# double-tube-iv.net
KiCad netlist of a schematic drawn in EAGLE
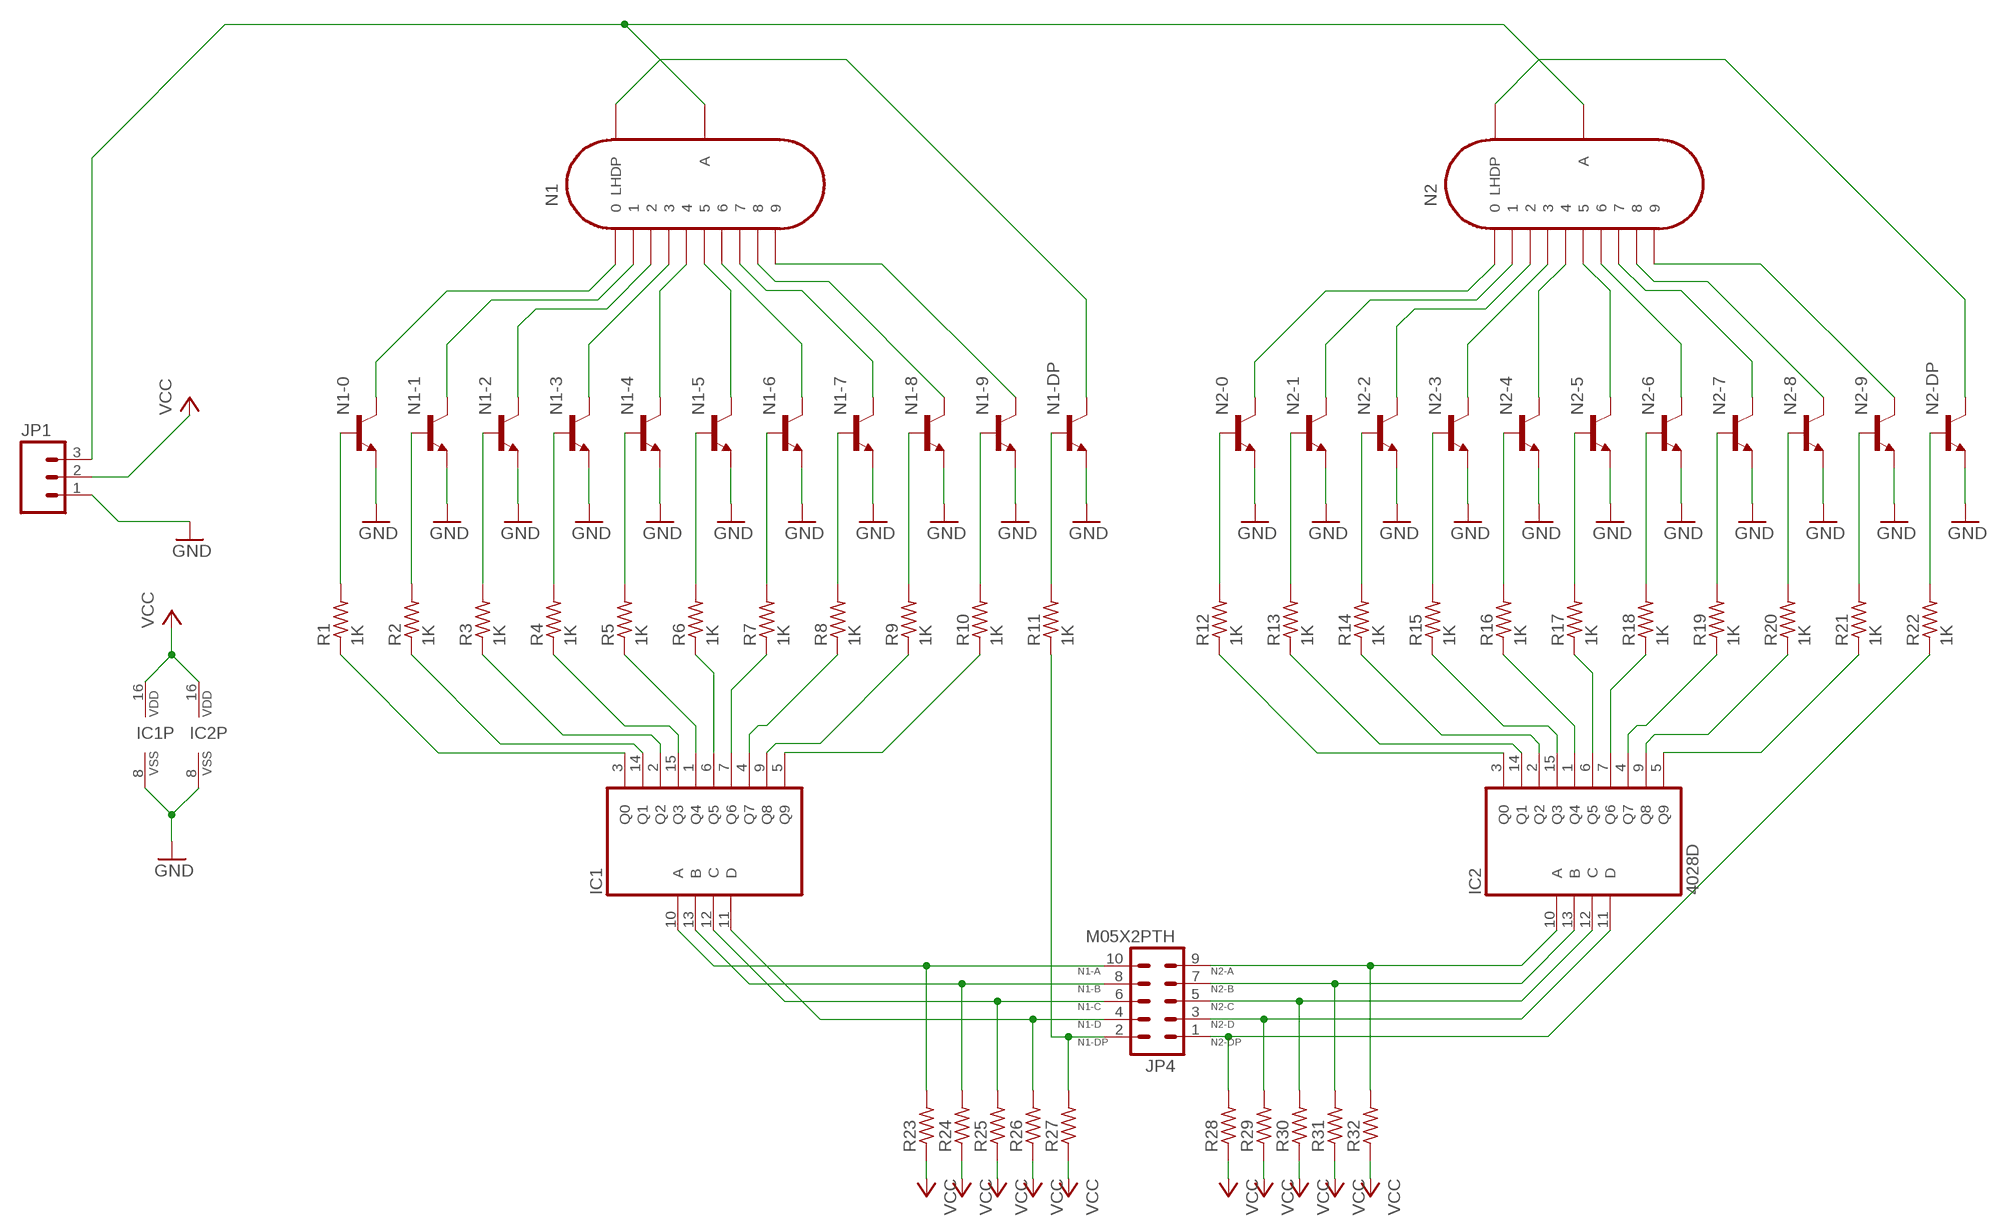
[diagram p0: schematic, sheet 1]

(export (version "E")
  (design (tool "Eeschema 10.0.6"))
  (components
    (comp (ref "IC1")
      (value "4028D")
      (footprint "eagle-import:SO16")
      (libsource (lib "eagle-import") (part "4028D"))
    )
    (comp (ref "IC2")
      (value "4028D")
      (footprint "eagle-import:SO16")
      (libsource (lib "eagle-import") (part "4028D"))
    )
    (comp (ref "JP1")
      (value "M03PTH")
      (footprint "eagle-import:1X03")
      (libsource (lib "eagle-import") (part "M03PTH"))
    )
    (comp (ref "JP4")
      (value "M05X2PTH")
      (footprint "eagle-import:AVR_ICSP")
      (libsource (lib "eagle-import") (part "M05X2PTH"))
    )
    (comp (ref "N1")
      (value "IN-12B")
      (footprint "eagle-import:IN-12")
      (libsource (lib "eagle-import") (part "IN-12B"))
    )
    (comp (ref "N1-0")
      (value "NPN_SMD")
      (footprint "eagle-import:SOT-23")
      (libsource (lib "eagle-import") (part "NPN_SMD"))
    )
    (comp (ref "N1-1")
      (value "NPN_SMD")
      (footprint "eagle-import:SOT-23")
      (libsource (lib "eagle-import") (part "NPN_SMD"))
    )
    (comp (ref "N1-2")
      (value "NPN_SMD")
      (footprint "eagle-import:SOT-23")
      (libsource (lib "eagle-import") (part "NPN_SMD"))
    )
    (comp (ref "N1-3")
      (value "NPN_SMD")
      (footprint "eagle-import:SOT-23")
      (libsource (lib "eagle-import") (part "NPN_SMD"))
    )
    (comp (ref "N1-4")
      (value "NPN_SMD")
      (footprint "eagle-import:SOT-23")
      (libsource (lib "eagle-import") (part "NPN_SMD"))
    )
    (comp (ref "N1-5")
      (value "NPN_SMD")
      (footprint "eagle-import:SOT-23")
      (libsource (lib "eagle-import") (part "NPN_SMD"))
    )
    (comp (ref "N1-6")
      (value "NPN_SMD")
      (footprint "eagle-import:SOT-23")
      (libsource (lib "eagle-import") (part "NPN_SMD"))
    )
    (comp (ref "N1-7")
      (value "NPN_SMD")
      (footprint "eagle-import:SOT-23")
      (libsource (lib "eagle-import") (part "NPN_SMD"))
    )
    (comp (ref "N1-8")
      (value "NPN_SMD")
      (footprint "eagle-import:SOT-23")
      (libsource (lib "eagle-import") (part "NPN_SMD"))
    )
    (comp (ref "N1-9")
      (value "NPN_SMD")
      (footprint "eagle-import:SOT-23")
      (libsource (lib "eagle-import") (part "NPN_SMD"))
    )
    (comp (ref "N1-DP")
      (value "NPN_SMD")
      (footprint "eagle-import:SOT-23")
      (libsource (lib "eagle-import") (part "NPN_SMD"))
    )
    (comp (ref "N2")
      (value "IN-12B")
      (footprint "eagle-import:IN-12")
      (libsource (lib "eagle-import") (part "IN-12B"))
    )
    (comp (ref "N2-0")
      (value "NPN_SMD")
      (footprint "eagle-import:SOT-23")
      (libsource (lib "eagle-import") (part "NPN_SMD"))
    )
    (comp (ref "N2-1")
      (value "NPN_SMD")
      (footprint "eagle-import:SOT-23")
      (libsource (lib "eagle-import") (part "NPN_SMD"))
    )
    (comp (ref "N2-2")
      (value "NPN_SMD")
      (footprint "eagle-import:SOT-23")
      (libsource (lib "eagle-import") (part "NPN_SMD"))
    )
    (comp (ref "N2-3")
      (value "NPN_SMD")
      (footprint "eagle-import:SOT-23")
      (libsource (lib "eagle-import") (part "NPN_SMD"))
    )
    (comp (ref "N2-4")
      (value "NPN_SMD")
      (footprint "eagle-import:SOT-23")
      (libsource (lib "eagle-import") (part "NPN_SMD"))
    )
    (comp (ref "N2-5")
      (value "NPN_SMD")
      (footprint "eagle-import:SOT-23")
      (libsource (lib "eagle-import") (part "NPN_SMD"))
    )
    (comp (ref "N2-6")
      (value "NPN_SMD")
      (footprint "eagle-import:SOT-23")
      (libsource (lib "eagle-import") (part "NPN_SMD"))
    )
    (comp (ref "N2-7")
      (value "NPN_SMD")
      (footprint "eagle-import:SOT-23")
      (libsource (lib "eagle-import") (part "NPN_SMD"))
    )
    (comp (ref "N2-8")
      (value "NPN_SMD")
      (footprint "eagle-import:SOT-23")
      (libsource (lib "eagle-import") (part "NPN_SMD"))
    )
    (comp (ref "N2-9")
      (value "NPN_SMD")
      (footprint "eagle-import:SOT-23")
      (libsource (lib "eagle-import") (part "NPN_SMD"))
    )
    (comp (ref "N2-DP")
      (value "NPN_SMD")
      (footprint "eagle-import:SOT-23")
      (libsource (lib "eagle-import") (part "NPN_SMD"))
    )
    (comp (ref "R1")
      (value "1K")
      (footprint "eagle-import:R0603")
      (libsource (lib "eagle-import") (part "RESISTORR0603"))
    )
    (comp (ref "R2")
      (value "1K")
      (footprint "eagle-import:R0603")
      (libsource (lib "eagle-import") (part "RESISTORR0603"))
    )
    (comp (ref "R3")
      (value "1K")
      (footprint "eagle-import:R0603")
      (libsource (lib "eagle-import") (part "RESISTORR0603"))
    )
    (comp (ref "R4")
      (value "1K")
      (footprint "eagle-import:R0603")
      (libsource (lib "eagle-import") (part "RESISTORR0603"))
    )
    (comp (ref "R5")
      (value "1K")
      (footprint "eagle-import:R0603")
      (libsource (lib "eagle-import") (part "RESISTORR0603"))
    )
    (comp (ref "R6")
      (value "1K")
      (footprint "eagle-import:R0603")
      (libsource (lib "eagle-import") (part "RESISTORR0603"))
    )
    (comp (ref "R7")
      (value "1K")
      (footprint "eagle-import:R0603")
      (libsource (lib "eagle-import") (part "RESISTORR0603"))
    )
    (comp (ref "R8")
      (value "1K")
      (footprint "eagle-import:R0603")
      (libsource (lib "eagle-import") (part "RESISTORR0603"))
    )
    (comp (ref "R9")
      (value "1K")
      (footprint "eagle-import:R0603")
      (libsource (lib "eagle-import") (part "RESISTORR0603"))
    )
    (comp (ref "R10")
      (value "1K")
      (footprint "eagle-import:R0603")
      (libsource (lib "eagle-import") (part "RESISTORR0603"))
    )
    (comp (ref "R11")
      (value "1K")
      (footprint "eagle-import:R0603")
      (libsource (lib "eagle-import") (part "RESISTORR0603"))
    )
    (comp (ref "R12")
      (value "1K")
      (footprint "eagle-import:R0603")
      (libsource (lib "eagle-import") (part "RESISTORR0603"))
    )
    (comp (ref "R13")
      (value "1K")
      (footprint "eagle-import:R0603")
      (libsource (lib "eagle-import") (part "RESISTORR0603"))
    )
    (comp (ref "R14")
      (value "1K")
      (footprint "eagle-import:R0603")
      (libsource (lib "eagle-import") (part "RESISTORR0603"))
    )
    (comp (ref "R15")
      (value "1K")
      (footprint "eagle-import:R0603")
      (libsource (lib "eagle-import") (part "RESISTORR0603"))
    )
    (comp (ref "R16")
      (value "1K")
      (footprint "eagle-import:R0603")
      (libsource (lib "eagle-import") (part "RESISTORR0603"))
    )
    (comp (ref "R17")
      (value "1K")
      (footprint "eagle-import:R0603")
      (libsource (lib "eagle-import") (part "RESISTORR0603"))
    )
    (comp (ref "R18")
      (value "1K")
      (footprint "eagle-import:R0603")
      (libsource (lib "eagle-import") (part "RESISTORR0603"))
    )
    (comp (ref "R19")
      (value "1K")
      (footprint "eagle-import:R0603")
      (libsource (lib "eagle-import") (part "RESISTORR0603"))
    )
    (comp (ref "R20")
      (value "1K")
      (footprint "eagle-import:R0603")
      (libsource (lib "eagle-import") (part "RESISTORR0603"))
    )
    (comp (ref "R21")
      (value "1K")
      (footprint "eagle-import:R0603")
      (libsource (lib "eagle-import") (part "RESISTORR0603"))
    )
    (comp (ref "R22")
      (value "1K")
      (footprint "eagle-import:R0603")
      (libsource (lib "eagle-import") (part "RESISTORR0603"))
    )
    (comp (ref "R23")
      (value "RESISTORR0603")
      (footprint "eagle-import:R0603")
      (libsource (lib "eagle-import") (part "RESISTORR0603"))
    )
    (comp (ref "R24")
      (value "RESISTORR0603")
      (footprint "eagle-import:R0603")
      (libsource (lib "eagle-import") (part "RESISTORR0603"))
    )
    (comp (ref "R25")
      (value "RESISTORR0603")
      (footprint "eagle-import:R0603")
      (libsource (lib "eagle-import") (part "RESISTORR0603"))
    )
    (comp (ref "R26")
      (value "RESISTORR0603")
      (footprint "eagle-import:R0603")
      (libsource (lib "eagle-import") (part "RESISTORR0603"))
    )
    (comp (ref "R27")
      (value "RESISTORR0603")
      (footprint "eagle-import:R0603")
      (libsource (lib "eagle-import") (part "RESISTORR0603"))
    )
    (comp (ref "R28")
      (value "RESISTORR0603")
      (footprint "eagle-import:R0603")
      (libsource (lib "eagle-import") (part "RESISTORR0603"))
    )
    (comp (ref "R29")
      (value "RESISTORR0603")
      (footprint "eagle-import:R0603")
      (libsource (lib "eagle-import") (part "RESISTORR0603"))
    )
    (comp (ref "R30")
      (value "RESISTORR0603")
      (footprint "eagle-import:R0603")
      (libsource (lib "eagle-import") (part "RESISTORR0603"))
    )
    (comp (ref "R31")
      (value "RESISTORR0603")
      (footprint "eagle-import:R0603")
      (libsource (lib "eagle-import") (part "RESISTORR0603"))
    )
    (comp (ref "R32")
      (value "RESISTORR0603")
      (footprint "eagle-import:R0603")
      (libsource (lib "eagle-import") (part "RESISTORR0603"))
    )
  )
  (nets
    (net (code "1") (name "/N1-A") (class "Default")
      (node (ref "IC1") (pin "10") (pinfunction "A_10") (pintype "input"))
      (node (ref "JP4") (pin "10") (pinfunction "10_10") (pintype "passive"))
      (node (ref "R23") (pin "2") (pinfunction "2_2") (pintype "passive"))
    )
    (net (code "2") (name "/N1-B") (class "Default")
      (node (ref "IC1") (pin "13") (pinfunction "B_13") (pintype "input"))
      (node (ref "JP4") (pin "8") (pinfunction "8_8") (pintype "passive"))
      (node (ref "R24") (pin "2") (pinfunction "2_2") (pintype "passive"))
    )
    (net (code "3") (name "/N1-C") (class "Default")
      (node (ref "IC1") (pin "12") (pinfunction "C_12") (pintype "input"))
      (node (ref "JP4") (pin "6") (pinfunction "6_6") (pintype "passive"))
      (node (ref "R25") (pin "2") (pinfunction "2_2") (pintype "passive"))
    )
    (net (code "4") (name "/N1-D") (class "Default")
      (node (ref "IC1") (pin "11") (pinfunction "D_11") (pintype "input"))
      (node (ref "JP4") (pin "4") (pinfunction "4_4") (pintype "passive"))
      (node (ref "R26") (pin "2") (pinfunction "2_2") (pintype "passive"))
    )
    (net (code "5") (name "/N1-DP") (class "Default")
      (node (ref "JP4") (pin "2") (pinfunction "2_2") (pintype "passive"))
      (node (ref "R11") (pin "1") (pinfunction "1_1") (pintype "passive"))
      (node (ref "R27") (pin "2") (pinfunction "2_2") (pintype "passive"))
    )
    (net (code "6") (name "/N2-A") (class "Default")
      (node (ref "IC2") (pin "10") (pinfunction "A_10") (pintype "input"))
      (node (ref "JP4") (pin "9") (pinfunction "9_9") (pintype "passive"))
      (node (ref "R32") (pin "2") (pinfunction "2_2") (pintype "passive"))
    )
    (net (code "7") (name "/N2-B") (class "Default")
      (node (ref "IC2") (pin "13") (pinfunction "B_13") (pintype "input"))
      (node (ref "JP4") (pin "7") (pinfunction "7_7") (pintype "passive"))
      (node (ref "R31") (pin "2") (pinfunction "2_2") (pintype "passive"))
    )
    (net (code "8") (name "/N2-C") (class "Default")
      (node (ref "IC2") (pin "12") (pinfunction "C_12") (pintype "input"))
      (node (ref "JP4") (pin "5") (pinfunction "5_5") (pintype "passive"))
      (node (ref "R30") (pin "2") (pinfunction "2_2") (pintype "passive"))
    )
    (net (code "9") (name "/N2-D") (class "Default")
      (node (ref "IC2") (pin "11") (pinfunction "D_11") (pintype "input"))
      (node (ref "JP4") (pin "3") (pinfunction "3_3") (pintype "passive"))
      (node (ref "R29") (pin "2") (pinfunction "2_2") (pintype "passive"))
    )
    (net (code "10") (name "/N2-DP") (class "Default")
      (node (ref "JP4") (pin "1") (pinfunction "1_1") (pintype "passive"))
      (node (ref "R22") (pin "1") (pinfunction "1_1") (pintype "passive"))
      (node (ref "R28") (pin "2") (pinfunction "2_2") (pintype "passive"))
    )
    (net (code "11") (name "GND") (class "Default")
      (node (ref "IC1") (pin "8") (pinfunction "VSS_8") (pintype "power_in"))
      (node (ref "IC2") (pin "8") (pinfunction "VSS_8") (pintype "power_in"))
      (node (ref "JP1") (pin "1") (pinfunction "1_1") (pintype "passive"))
      (node (ref "N1-0") (pin "2") (pinfunction "E_2") (pintype "passive"))
      (node (ref "N1-1") (pin "2") (pinfunction "E_2") (pintype "passive"))
      (node (ref "N1-2") (pin "2") (pinfunction "E_2") (pintype "passive"))
      (node (ref "N1-3") (pin "2") (pinfunction "E_2") (pintype "passive"))
      (node (ref "N1-4") (pin "2") (pinfunction "E_2") (pintype "passive"))
      (node (ref "N1-5") (pin "2") (pinfunction "E_2") (pintype "passive"))
      (node (ref "N1-6") (pin "2") (pinfunction "E_2") (pintype "passive"))
      (node (ref "N1-7") (pin "2") (pinfunction "E_2") (pintype "passive"))
      (node (ref "N1-8") (pin "2") (pinfunction "E_2") (pintype "passive"))
      (node (ref "N1-9") (pin "2") (pinfunction "E_2") (pintype "passive"))
      (node (ref "N1-DP") (pin "2") (pinfunction "E_2") (pintype "passive"))
      (node (ref "N2-0") (pin "2") (pinfunction "E_2") (pintype "passive"))
      (node (ref "N2-1") (pin "2") (pinfunction "E_2") (pintype "passive"))
      (node (ref "N2-2") (pin "2") (pinfunction "E_2") (pintype "passive"))
      (node (ref "N2-3") (pin "2") (pinfunction "E_2") (pintype "passive"))
      (node (ref "N2-4") (pin "2") (pinfunction "E_2") (pintype "passive"))
      (node (ref "N2-5") (pin "2") (pinfunction "E_2") (pintype "passive"))
      (node (ref "N2-6") (pin "2") (pinfunction "E_2") (pintype "passive"))
      (node (ref "N2-7") (pin "2") (pinfunction "E_2") (pintype "passive"))
      (node (ref "N2-8") (pin "2") (pinfunction "E_2") (pintype "passive"))
      (node (ref "N2-9") (pin "2") (pinfunction "E_2") (pintype "passive"))
      (node (ref "N2-DP") (pin "2") (pinfunction "E_2") (pintype "passive"))
    )
    (net (code "12") (name "Net-(IC1A-Q0)") (class "Default")
      (node (ref "IC1") (pin "3") (pinfunction "Q0_3") (pintype "output"))
      (node (ref "R1") (pin "1") (pinfunction "1_1") (pintype "passive"))
    )
    (net (code "13") (name "Net-(IC1A-Q1)") (class "Default")
      (node (ref "IC1") (pin "14") (pinfunction "Q1_14") (pintype "output"))
      (node (ref "R2") (pin "1") (pinfunction "1_1") (pintype "passive"))
    )
    (net (code "14") (name "Net-(IC1A-Q2)") (class "Default")
      (node (ref "IC1") (pin "2") (pinfunction "Q2_2") (pintype "output"))
      (node (ref "R3") (pin "1") (pinfunction "1_1") (pintype "passive"))
    )
    (net (code "15") (name "Net-(IC1A-Q3)") (class "Default")
      (node (ref "IC1") (pin "15") (pinfunction "Q3_15") (pintype "output"))
      (node (ref "R4") (pin "1") (pinfunction "1_1") (pintype "passive"))
    )
    (net (code "16") (name "Net-(IC1A-Q4)") (class "Default")
      (node (ref "IC1") (pin "1") (pinfunction "Q4_1") (pintype "output"))
      (node (ref "R5") (pin "1") (pinfunction "1_1") (pintype "passive"))
    )
    (net (code "17") (name "Net-(IC1A-Q5)") (class "Default")
      (node (ref "IC1") (pin "6") (pinfunction "Q5_6") (pintype "output"))
      (node (ref "R6") (pin "1") (pinfunction "1_1") (pintype "passive"))
    )
    (net (code "18") (name "Net-(IC1A-Q6)") (class "Default")
      (node (ref "IC1") (pin "7") (pinfunction "Q6_7") (pintype "output"))
      (node (ref "R7") (pin "1") (pinfunction "1_1") (pintype "passive"))
    )
    (net (code "19") (name "Net-(IC1A-Q7)") (class "Default")
      (node (ref "IC1") (pin "4") (pinfunction "Q7_4") (pintype "output"))
      (node (ref "R8") (pin "1") (pinfunction "1_1") (pintype "passive"))
    )
    (net (code "20") (name "Net-(IC1A-Q8)") (class "Default")
      (node (ref "IC1") (pin "9") (pinfunction "Q8_9") (pintype "output"))
      (node (ref "R9") (pin "1") (pinfunction "1_1") (pintype "passive"))
    )
    (net (code "21") (name "Net-(IC1A-Q9)") (class "Default")
      (node (ref "IC1") (pin "5") (pinfunction "Q9_5") (pintype "output"))
      (node (ref "R10") (pin "1") (pinfunction "1_1") (pintype "passive"))
    )
    (net (code "22") (name "Net-(IC2A-Q0)") (class "Default")
      (node (ref "IC2") (pin "3") (pinfunction "Q0_3") (pintype "output"))
      (node (ref "R12") (pin "1") (pinfunction "1_1") (pintype "passive"))
    )
    (net (code "23") (name "Net-(IC2A-Q1)") (class "Default")
      (node (ref "IC2") (pin "14") (pinfunction "Q1_14") (pintype "output"))
      (node (ref "R13") (pin "1") (pinfunction "1_1") (pintype "passive"))
    )
    (net (code "24") (name "Net-(IC2A-Q2)") (class "Default")
      (node (ref "IC2") (pin "2") (pinfunction "Q2_2") (pintype "output"))
      (node (ref "R14") (pin "1") (pinfunction "1_1") (pintype "passive"))
    )
    (net (code "25") (name "Net-(IC2A-Q3)") (class "Default")
      (node (ref "IC2") (pin "15") (pinfunction "Q3_15") (pintype "output"))
      (node (ref "R15") (pin "1") (pinfunction "1_1") (pintype "passive"))
    )
    (net (code "26") (name "Net-(IC2A-Q4)") (class "Default")
      (node (ref "IC2") (pin "1") (pinfunction "Q4_1") (pintype "output"))
      (node (ref "R16") (pin "1") (pinfunction "1_1") (pintype "passive"))
    )
    (net (code "27") (name "Net-(IC2A-Q5)") (class "Default")
      (node (ref "IC2") (pin "6") (pinfunction "Q5_6") (pintype "output"))
      (node (ref "R17") (pin "1") (pinfunction "1_1") (pintype "passive"))
    )
    (net (code "28") (name "Net-(IC2A-Q6)") (class "Default")
      (node (ref "IC2") (pin "7") (pinfunction "Q6_7") (pintype "output"))
      (node (ref "R18") (pin "1") (pinfunction "1_1") (pintype "passive"))
    )
    (net (code "29") (name "Net-(IC2A-Q7)") (class "Default")
      (node (ref "IC2") (pin "4") (pinfunction "Q7_4") (pintype "output"))
      (node (ref "R19") (pin "1") (pinfunction "1_1") (pintype "passive"))
    )
    (net (code "30") (name "Net-(IC2A-Q8)") (class "Default")
      (node (ref "IC2") (pin "9") (pinfunction "Q8_9") (pintype "output"))
      (node (ref "R20") (pin "1") (pinfunction "1_1") (pintype "passive"))
    )
    (net (code "31") (name "Net-(IC2A-Q9)") (class "Default")
      (node (ref "IC2") (pin "5") (pinfunction "Q9_5") (pintype "output"))
      (node (ref "R21") (pin "1") (pinfunction "1_1") (pintype "passive"))
    )
    (net (code "32") (name "Net-(JP1-Pad3)") (class "Default")
      (node (ref "JP1") (pin "3") (pinfunction "3_3") (pintype "passive"))
      (node (ref "N1") (pin "A") (pinfunction "A_A") (pintype "bidirectional"))
      (node (ref "N2") (pin "A") (pinfunction "A_A") (pintype "bidirectional"))
    )
    (net (code "33") (name "Net-(N1-0-B)") (class "Default")
      (node (ref "N1-0") (pin "1") (pinfunction "B_1") (pintype "passive"))
      (node (ref "R1") (pin "2") (pinfunction "2_2") (pintype "passive"))
    )
    (net (code "34") (name "Net-(N1-0-C)") (class "Default")
      (node (ref "N1") (pin "0") (pinfunction "0_0") (pintype "bidirectional"))
      (node (ref "N1-0") (pin "3") (pinfunction "C_3") (pintype "passive"))
    )
    (net (code "35") (name "Net-(N1-1-B)") (class "Default")
      (node (ref "N1-1") (pin "1") (pinfunction "B_1") (pintype "passive"))
      (node (ref "R2") (pin "2") (pinfunction "2_2") (pintype "passive"))
    )
    (net (code "36") (name "Net-(N1-1-C)") (class "Default")
      (node (ref "N1") (pin "1") (pinfunction "1_1") (pintype "bidirectional"))
      (node (ref "N1-1") (pin "3") (pinfunction "C_3") (pintype "passive"))
    )
    (net (code "37") (name "Net-(N1-2-B)") (class "Default")
      (node (ref "N1-2") (pin "1") (pinfunction "B_1") (pintype "passive"))
      (node (ref "R3") (pin "2") (pinfunction "2_2") (pintype "passive"))
    )
    (net (code "38") (name "Net-(N1-2-C)") (class "Default")
      (node (ref "N1") (pin "2") (pinfunction "2_2") (pintype "bidirectional"))
      (node (ref "N1-2") (pin "3") (pinfunction "C_3") (pintype "passive"))
    )
    (net (code "39") (name "Net-(N1-3-B)") (class "Default")
      (node (ref "N1-3") (pin "1") (pinfunction "B_1") (pintype "passive"))
      (node (ref "R4") (pin "2") (pinfunction "2_2") (pintype "passive"))
    )
    (net (code "40") (name "Net-(N1-3-C)") (class "Default")
      (node (ref "N1") (pin "3") (pinfunction "3_3") (pintype "bidirectional"))
      (node (ref "N1-3") (pin "3") (pinfunction "C_3") (pintype "passive"))
    )
    (net (code "41") (name "Net-(N1-4-B)") (class "Default")
      (node (ref "N1-4") (pin "1") (pinfunction "B_1") (pintype "passive"))
      (node (ref "R5") (pin "2") (pinfunction "2_2") (pintype "passive"))
    )
    (net (code "42") (name "Net-(N1-4-C)") (class "Default")
      (node (ref "N1") (pin "4") (pinfunction "4_4") (pintype "bidirectional"))
      (node (ref "N1-4") (pin "3") (pinfunction "C_3") (pintype "passive"))
    )
    (net (code "43") (name "Net-(N1-5-B)") (class "Default")
      (node (ref "N1-5") (pin "1") (pinfunction "B_1") (pintype "passive"))
      (node (ref "R6") (pin "2") (pinfunction "2_2") (pintype "passive"))
    )
    (net (code "44") (name "Net-(N1-5-C)") (class "Default")
      (node (ref "N1") (pin "5") (pinfunction "5_5") (pintype "bidirectional"))
      (node (ref "N1-5") (pin "3") (pinfunction "C_3") (pintype "passive"))
    )
    (net (code "45") (name "Net-(N1-6-B)") (class "Default")
      (node (ref "N1-6") (pin "1") (pinfunction "B_1") (pintype "passive"))
      (node (ref "R7") (pin "2") (pinfunction "2_2") (pintype "passive"))
    )
    (net (code "46") (name "Net-(N1-6-C)") (class "Default")
      (node (ref "N1") (pin "6") (pinfunction "6_6") (pintype "bidirectional"))
      (node (ref "N1-6") (pin "3") (pinfunction "C_3") (pintype "passive"))
    )
    (net (code "47") (name "Net-(N1-7-B)") (class "Default")
      (node (ref "N1-7") (pin "1") (pinfunction "B_1") (pintype "passive"))
      (node (ref "R8") (pin "2") (pinfunction "2_2") (pintype "passive"))
    )
    (net (code "48") (name "Net-(N1-7-C)") (class "Default")
      (node (ref "N1") (pin "7") (pinfunction "7_7") (pintype "bidirectional"))
      (node (ref "N1-7") (pin "3") (pinfunction "C_3") (pintype "passive"))
    )
    (net (code "49") (name "Net-(N1-8-B)") (class "Default")
      (node (ref "N1-8") (pin "1") (pinfunction "B_1") (pintype "passive"))
      (node (ref "R9") (pin "2") (pinfunction "2_2") (pintype "passive"))
    )
    (net (code "50") (name "Net-(N1-8-C)") (class "Default")
      (node (ref "N1") (pin "8") (pinfunction "8_8") (pintype "bidirectional"))
      (node (ref "N1-8") (pin "3") (pinfunction "C_3") (pintype "passive"))
    )
    (net (code "51") (name "Net-(N1-9-B)") (class "Default")
      (node (ref "N1-9") (pin "1") (pinfunction "B_1") (pintype "passive"))
      (node (ref "R10") (pin "2") (pinfunction "2_2") (pintype "passive"))
    )
    (net (code "52") (name "Net-(N1-9-C)") (class "Default")
      (node (ref "N1") (pin "9") (pinfunction "9_9") (pintype "bidirectional"))
      (node (ref "N1-9") (pin "3") (pinfunction "C_3") (pintype "passive"))
    )
    (net (code "53") (name "Net-(N1-DP-B)") (class "Default")
      (node (ref "N1-DP") (pin "1") (pinfunction "B_1") (pintype "passive"))
      (node (ref "R11") (pin "2") (pinfunction "2_2") (pintype "passive"))
    )
    (net (code "54") (name "Net-(N1-DP-C)") (class "Default")
      (node (ref "N1") (pin "LHDP") (pinfunction "LHDP_LHDP") (pintype "bidirectional"))
      (node (ref "N1-DP") (pin "3") (pinfunction "C_3") (pintype "passive"))
    )
    (net (code "55") (name "Net-(N2-0-B)") (class "Default")
      (node (ref "N2-0") (pin "1") (pinfunction "B_1") (pintype "passive"))
      (node (ref "R12") (pin "2") (pinfunction "2_2") (pintype "passive"))
    )
    (net (code "56") (name "Net-(N2-0-C)") (class "Default")
      (node (ref "N2") (pin "0") (pinfunction "0_0") (pintype "bidirectional"))
      (node (ref "N2-0") (pin "3") (pinfunction "C_3") (pintype "passive"))
    )
    (net (code "57") (name "Net-(N2-1-B)") (class "Default")
      (node (ref "N2-1") (pin "1") (pinfunction "B_1") (pintype "passive"))
      (node (ref "R13") (pin "2") (pinfunction "2_2") (pintype "passive"))
    )
    (net (code "58") (name "Net-(N2-1-C)") (class "Default")
      (node (ref "N2") (pin "1") (pinfunction "1_1") (pintype "bidirectional"))
      (node (ref "N2-1") (pin "3") (pinfunction "C_3") (pintype "passive"))
    )
    (net (code "59") (name "Net-(N2-2-B)") (class "Default")
      (node (ref "N2-2") (pin "1") (pinfunction "B_1") (pintype "passive"))
      (node (ref "R14") (pin "2") (pinfunction "2_2") (pintype "passive"))
    )
    (net (code "60") (name "Net-(N2-2-C)") (class "Default")
      (node (ref "N2") (pin "2") (pinfunction "2_2") (pintype "bidirectional"))
      (node (ref "N2-2") (pin "3") (pinfunction "C_3") (pintype "passive"))
    )
    (net (code "61") (name "Net-(N2-3-B)") (class "Default")
      (node (ref "N2-3") (pin "1") (pinfunction "B_1") (pintype "passive"))
      (node (ref "R15") (pin "2") (pinfunction "2_2") (pintype "passive"))
    )
    (net (code "62") (name "Net-(N2-3-C)") (class "Default")
      (node (ref "N2") (pin "3") (pinfunction "3_3") (pintype "bidirectional"))
      (node (ref "N2-3") (pin "3") (pinfunction "C_3") (pintype "passive"))
    )
    (net (code "63") (name "Net-(N2-4-B)") (class "Default")
      (node (ref "N2-4") (pin "1") (pinfunction "B_1") (pintype "passive"))
      (node (ref "R16") (pin "2") (pinfunction "2_2") (pintype "passive"))
    )
    (net (code "64") (name "Net-(N2-4-C)") (class "Default")
      (node (ref "N2") (pin "4") (pinfunction "4_4") (pintype "bidirectional"))
      (node (ref "N2-4") (pin "3") (pinfunction "C_3") (pintype "passive"))
    )
    (net (code "65") (name "Net-(N2-5-B)") (class "Default")
      (node (ref "N2-5") (pin "1") (pinfunction "B_1") (pintype "passive"))
      (node (ref "R17") (pin "2") (pinfunction "2_2") (pintype "passive"))
    )
    (net (code "66") (name "Net-(N2-5-C)") (class "Default")
      (node (ref "N2") (pin "5") (pinfunction "5_5") (pintype "bidirectional"))
      (node (ref "N2-5") (pin "3") (pinfunction "C_3") (pintype "passive"))
    )
    (net (code "67") (name "Net-(N2-6-B)") (class "Default")
      (node (ref "N2-6") (pin "1") (pinfunction "B_1") (pintype "passive"))
      (node (ref "R18") (pin "2") (pinfunction "2_2") (pintype "passive"))
    )
    (net (code "68") (name "Net-(N2-6-C)") (class "Default")
      (node (ref "N2") (pin "6") (pinfunction "6_6") (pintype "bidirectional"))
      (node (ref "N2-6") (pin "3") (pinfunction "C_3") (pintype "passive"))
    )
    (net (code "69") (name "Net-(N2-7-B)") (class "Default")
      (node (ref "N2-7") (pin "1") (pinfunction "B_1") (pintype "passive"))
      (node (ref "R19") (pin "2") (pinfunction "2_2") (pintype "passive"))
    )
    (net (code "70") (name "Net-(N2-7-C)") (class "Default")
      (node (ref "N2") (pin "7") (pinfunction "7_7") (pintype "bidirectional"))
      (node (ref "N2-7") (pin "3") (pinfunction "C_3") (pintype "passive"))
    )
    (net (code "71") (name "Net-(N2-8-B)") (class "Default")
      (node (ref "N2-8") (pin "1") (pinfunction "B_1") (pintype "passive"))
      (node (ref "R20") (pin "2") (pinfunction "2_2") (pintype "passive"))
    )
    (net (code "72") (name "Net-(N2-8-C)") (class "Default")
      (node (ref "N2") (pin "8") (pinfunction "8_8") (pintype "bidirectional"))
      (node (ref "N2-8") (pin "3") (pinfunction "C_3") (pintype "passive"))
    )
    (net (code "73") (name "Net-(N2-9-B)") (class "Default")
      (node (ref "N2-9") (pin "1") (pinfunction "B_1") (pintype "passive"))
      (node (ref "R21") (pin "2") (pinfunction "2_2") (pintype "passive"))
    )
    (net (code "74") (name "Net-(N2-9-C)") (class "Default")
      (node (ref "N2") (pin "9") (pinfunction "9_9") (pintype "bidirectional"))
      (node (ref "N2-9") (pin "3") (pinfunction "C_3") (pintype "passive"))
    )
    (net (code "75") (name "Net-(N2-DP-B)") (class "Default")
      (node (ref "N2-DP") (pin "1") (pinfunction "B_1") (pintype "passive"))
      (node (ref "R22") (pin "2") (pinfunction "2_2") (pintype "passive"))
    )
    (net (code "76") (name "Net-(N2-DP-C)") (class "Default")
      (node (ref "N2") (pin "LHDP") (pinfunction "LHDP_LHDP") (pintype "bidirectional"))
      (node (ref "N2-DP") (pin "3") (pinfunction "C_3") (pintype "passive"))
    )
    (net (code "77") (name "VCC") (class "Default")
      (node (ref "IC1") (pin "16") (pinfunction "VDD_16") (pintype "power_in"))
      (node (ref "IC2") (pin "16") (pinfunction "VDD_16") (pintype "power_in"))
      (node (ref "JP1") (pin "2") (pinfunction "2_2") (pintype "passive"))
      (node (ref "R23") (pin "1") (pinfunction "1_1") (pintype "passive"))
      (node (ref "R24") (pin "1") (pinfunction "1_1") (pintype "passive"))
      (node (ref "R25") (pin "1") (pinfunction "1_1") (pintype "passive"))
      (node (ref "R26") (pin "1") (pinfunction "1_1") (pintype "passive"))
      (node (ref "R27") (pin "1") (pinfunction "1_1") (pintype "passive"))
      (node (ref "R28") (pin "1") (pinfunction "1_1") (pintype "passive"))
      (node (ref "R29") (pin "1") (pinfunction "1_1") (pintype "passive"))
      (node (ref "R30") (pin "1") (pinfunction "1_1") (pintype "passive"))
      (node (ref "R31") (pin "1") (pinfunction "1_1") (pintype "passive"))
      (node (ref "R32") (pin "1") (pinfunction "1_1") (pintype "passive"))
    )
  )
)
